# ProProject__EDA__2023-12-29_2024-01-28.net
KiCad netlist of a schematic drawn in EasyEDA Pro
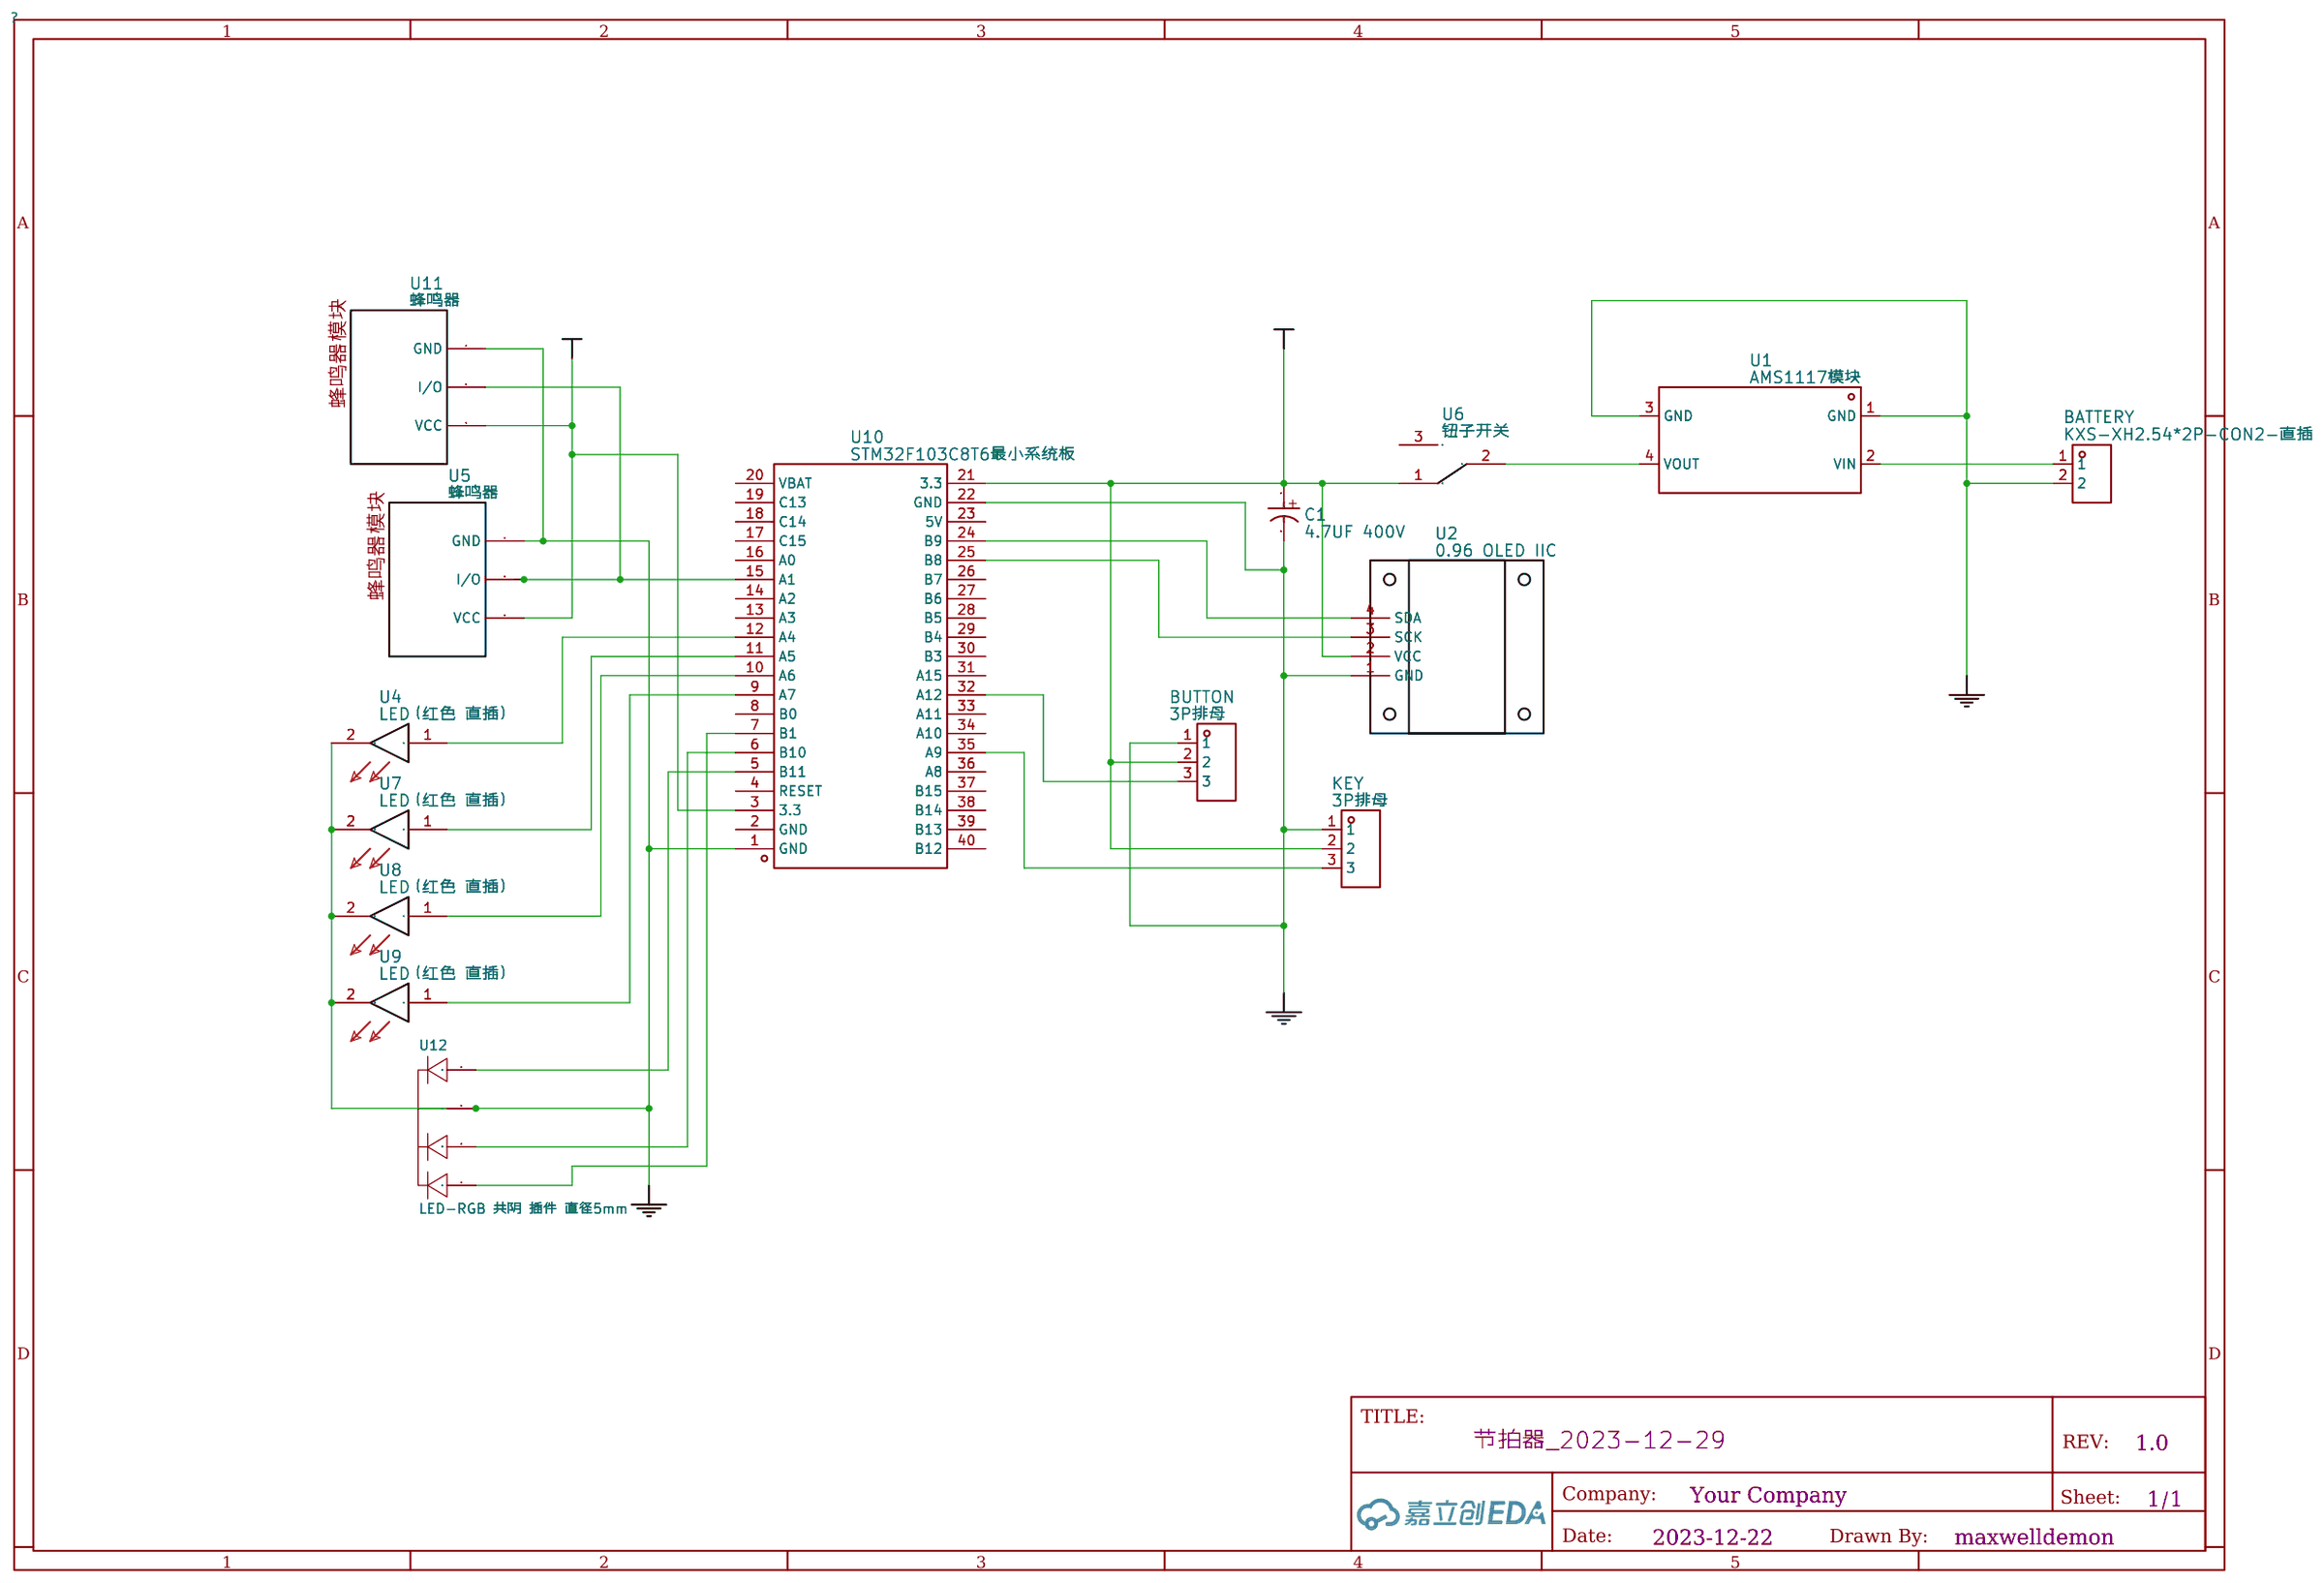
[diagram p0: schematic sheet]

(export (version "E")
  (design (tool "Eeschema 10.0.6"))
  (components
    (comp (ref "BATTERY")
      (value "KXS-XH2.54*2P-CON2-直插")
      (footprint "easyedapro:KXS-XH2.54-CONN-TH_XH2.54-2P")
      (fields (field (name "Manufacturer Part") "KXS-XH2.54*2P_直插"))
      (libsource (lib "easyedapro") (part "KXS-XH2.54*2P-CON2-直插"))
    )
    (comp (ref "BUTTON")
      (value "3P排母")
      (footprint "easyedapro:3P排母")
      (libsource (lib "easyedapro") (part "3P排母"))
    )
    (comp (ref "C1")
      (value "4.7UF 400V")
      (footprint "easyedapro:6X12")
      (libsource (lib "easyedapro") (part "4.7UF 400V"))
    )
    (comp (ref "KEY")
      (value "3P排母")
      (footprint "easyedapro:3P排母")
      (libsource (lib "easyedapro") (part "3P排母"))
    )
    (comp (ref "U1")
      (value "AMS1117模块")
      (footprint "easyedapro:_AMS1117模块")
      (libsource (lib "easyedapro") (part "AMS1117模块"))
    )
    (comp (ref "U2")
      (value "0.96 OLED IIC")
      (footprint "easyedapro:0.96寸OLED模块I2C")
      (fields (field (name "Manufacturer Part") "0.96 OLED"))
      (libsource (lib "easyedapro") (part "0.96 OLED IIC"))
    )
    (comp (ref "U4")
      (value "LED（红色 直插）")
      (footprint "easyedapro:LED直插")
      (libsource (lib "easyedapro") (part "LED（红色 直插）"))
    )
    (comp (ref "U5") (value "蜂鸣器") (footprint "easyedapro:蜂鸣器模块") (libsource (lib "easyedapro") (part "蜂鸣器")))
    (comp (ref "U6")
      (value "钮子开关")
      (footprint "easyedapro:钮子开关钮子开关三脚三档")
      (libsource (lib "easyedapro") (part "钮子开关"))
    )
    (comp (ref "U7")
      (value "LED（红色 直插）")
      (footprint "easyedapro:LED直插")
      (libsource (lib "easyedapro") (part "LED（红色 直插）"))
    )
    (comp (ref "U8")
      (value "LED（红色 直插）")
      (footprint "easyedapro:LED直插")
      (libsource (lib "easyedapro") (part "LED（红色 直插）"))
    )
    (comp (ref "U9")
      (value "LED（红色 直插）")
      (footprint "easyedapro:LED直插")
      (libsource (lib "easyedapro") (part "LED（红色 直插）"))
    )
    (comp (ref "U10")
      (value "STM32F103C8T6最小系统板")
      (footprint "easyedapro:STM32F103C8T6最小系统板PCB图")
      (libsource (lib "easyedapro") (part "STM32F103C8T6最小系统板"))
    )
    (comp (ref "U11")
      (value "蜂鸣器")
      (footprint "easyedapro:蜂鸣器模块")
      (libsource (lib "easyedapro") (part "蜂鸣器"))
    )
    (comp (ref "U12")
      (value "LED-RGB 共阴 插件 直径5mm")
      (footprint "easyedapro:LED-TH_4P-BD5.8-P1.30")
      (libsource (lib "easyedapro") (part "LED-RGB 共阴 插件 直径5MM"))
    )
  )
  (nets
    (net (code "1") (name "GND") (class "Default")
      (node (ref "BATTERY") (pin "2") (pinfunction "2_2") (pintype "unspecified"))
      (node (ref "BUTTON") (pin "1") (pinfunction "1_1") (pintype "unspecified"))
      (node (ref "C1") (pin "2") (pinfunction "2_2") (pintype "input"))
      (node (ref "KEY") (pin "1") (pinfunction "1_1") (pintype "unspecified"))
      (node (ref "U1") (pin "1") (pinfunction "GND_1") (pintype "unspecified"))
      (node (ref "U1") (pin "3") (pinfunction "GND_3") (pintype "unspecified"))
      (node (ref "U10") (pin "1") (pinfunction "GND_1") (pintype "unspecified"))
      (node (ref "U10") (pin "22") (pinfunction "GND_22") (pintype "unspecified"))
      (node (ref "U11") (pin "1") (pinfunction "GND_1") (pintype "unspecified"))
      (node (ref "U12") (pin "2") (pinfunction "-_2") (pintype "input"))
      (node (ref "U2") (pin "1") (pinfunction "GND_1") (pintype "unspecified"))
      (node (ref "U4") (pin "2") (pinfunction "2_2") (pintype "unspecified"))
      (node (ref "U5") (pin "1") (pinfunction "GND_1") (pintype "unspecified"))
      (node (ref "U7") (pin "2") (pinfunction "2_2") (pintype "unspecified"))
      (node (ref "U8") (pin "2") (pinfunction "2_2") (pintype "unspecified"))
      (node (ref "U9") (pin "2") (pinfunction "2_2") (pintype "unspecified"))
    )
    (net (code "2") (name "Net-(U1-VIN)") (class "Default")
      (node (ref "BATTERY") (pin "1") (pinfunction "1_1") (pintype "unspecified"))
      (node (ref "U1") (pin "2") (pinfunction "VIN_2") (pintype "unspecified"))
    )
    (net (code "3") (name "Net-(U1-VOUT)") (class "Default")
      (node (ref "U1") (pin "4") (pinfunction "VOUT_4") (pintype "unspecified"))
      (node (ref "U6") (pin "2") (pinfunction "1_2") (pintype "unspecified"))
    )
    (net (code "4") (name "Net-(U10-A1)") (class "Default")
      (node (ref "U10") (pin "15") (pinfunction "A1_15") (pintype "unspecified"))
      (node (ref "U11") (pin "2") (pinfunction "I/O_2") (pintype "unspecified"))
      (node (ref "U5") (pin "2") (pinfunction "I/O_2") (pintype "unspecified"))
    )
    (net (code "5") (name "Net-(U10-A4)") (class "Default")
      (node (ref "U10") (pin "12") (pinfunction "A4_12") (pintype "unspecified"))
      (node (ref "U4") (pin "1") (pinfunction "1_1") (pintype "unspecified"))
    )
    (net (code "6") (name "Net-(U10-A5)") (class "Default")
      (node (ref "U10") (pin "11") (pinfunction "A5_11") (pintype "unspecified"))
      (node (ref "U7") (pin "1") (pinfunction "1_1") (pintype "unspecified"))
    )
    (net (code "7") (name "Net-(U10-A6)") (class "Default")
      (node (ref "U10") (pin "10") (pinfunction "A6_10") (pintype "unspecified"))
      (node (ref "U8") (pin "1") (pinfunction "1_1") (pintype "unspecified"))
    )
    (net (code "8") (name "Net-(U10-A7)") (class "Default")
      (node (ref "U10") (pin "9") (pinfunction "A7_9") (pintype "unspecified"))
      (node (ref "U9") (pin "1") (pinfunction "1_1") (pintype "unspecified"))
    )
    (net (code "9") (name "Net-(U10-A9)") (class "Default")
      (node (ref "KEY") (pin "3") (pinfunction "3_3") (pintype "unspecified"))
      (node (ref "U10") (pin "35") (pinfunction "A9_35") (pintype "unspecified"))
    )
    (net (code "10") (name "Net-(U10-A12)") (class "Default")
      (node (ref "BUTTON") (pin "3") (pinfunction "3_3") (pintype "unspecified"))
      (node (ref "U10") (pin "32") (pinfunction "A12_32") (pintype "unspecified"))
    )
    (net (code "11") (name "Net-(U10-B1)") (class "Default")
      (node (ref "U10") (pin "7") (pinfunction "B1_7") (pintype "unspecified"))
      (node (ref "U12") (pin "4") (pinfunction "4_4") (pintype "input"))
    )
    (net (code "12") (name "Net-(U10-B8)") (class "Default")
      (node (ref "U10") (pin "25") (pinfunction "B8_25") (pintype "unspecified"))
      (node (ref "U2") (pin "3") (pinfunction "SCK_3") (pintype "unspecified"))
    )
    (net (code "13") (name "Net-(U10-B9)") (class "Default")
      (node (ref "U10") (pin "24") (pinfunction "B9_24") (pintype "unspecified"))
      (node (ref "U2") (pin "4") (pinfunction "SDA_4") (pintype "unspecified"))
    )
    (net (code "14") (name "Net-(U10-B10)") (class "Default")
      (node (ref "U10") (pin "6") (pinfunction "B10_6") (pintype "unspecified"))
      (node (ref "U12") (pin "3") (pinfunction "3_3") (pintype "input"))
    )
    (net (code "15") (name "Net-(U10-B11)") (class "Default")
      (node (ref "U10") (pin "5") (pinfunction "B11_5") (pintype "unspecified"))
      (node (ref "U12") (pin "1") (pinfunction "1_1") (pintype "input"))
    )
    (net (code "16") (name "VCC") (class "Default")
      (node (ref "BUTTON") (pin "2") (pinfunction "2_2") (pintype "unspecified"))
      (node (ref "C1") (pin "1") (pinfunction "1_1") (pintype "input"))
      (node (ref "KEY") (pin "2") (pinfunction "2_2") (pintype "unspecified"))
      (node (ref "U10") (pin "21") (pinfunction "3.3_21") (pintype "unspecified"))
      (node (ref "U10") (pin "3") (pinfunction "3.3_3") (pintype "unspecified"))
      (node (ref "U11") (pin "3") (pinfunction "VCC_3") (pintype "unspecified"))
      (node (ref "U2") (pin "2") (pinfunction "VCC_2") (pintype "unspecified"))
      (node (ref "U5") (pin "3") (pinfunction "VCC_3") (pintype "unspecified"))
      (node (ref "U6") (pin "1") (pinfunction "3_1") (pintype "unspecified"))
    )
    (net (code "17") (name "unconnected-(U6-4-Pad3)") (class "Default")
      (node (ref "U6") (pin "3") (pinfunction "4_3") (pintype "unspecified"))
    )
    (net (code "18") (name "unconnected-(U10-5V-Pad23)") (class "Default")
      (node (ref "U10") (pin "23") (pinfunction "5V_23") (pintype "unspecified"))
    )
    (net (code "19") (name "unconnected-(U10-A0-Pad16)") (class "Default")
      (node (ref "U10") (pin "16") (pinfunction "A0_16") (pintype "unspecified"))
    )
    (net (code "20") (name "unconnected-(U10-A2-Pad14)") (class "Default")
      (node (ref "U10") (pin "14") (pinfunction "A2_14") (pintype "unspecified"))
    )
    (net (code "21") (name "unconnected-(U10-A3-Pad13)") (class "Default")
      (node (ref "U10") (pin "13") (pinfunction "A3_13") (pintype "unspecified"))
    )
    (net (code "22") (name "unconnected-(U10-A8-Pad36)") (class "Default")
      (node (ref "U10") (pin "36") (pinfunction "A8_36") (pintype "unspecified"))
    )
    (net (code "23") (name "unconnected-(U10-A10-Pad34)") (class "Default")
      (node (ref "U10") (pin "34") (pinfunction "A10_34") (pintype "unspecified"))
    )
    (net (code "24") (name "unconnected-(U10-A11-Pad33)") (class "Default")
      (node (ref "U10") (pin "33") (pinfunction "A11_33") (pintype "unspecified"))
    )
    (net (code "25") (name "unconnected-(U10-A15-Pad31)") (class "Default")
      (node (ref "U10") (pin "31") (pinfunction "A15_31") (pintype "unspecified"))
    )
    (net (code "26") (name "unconnected-(U10-B0-Pad8)") (class "Default")
      (node (ref "U10") (pin "8") (pinfunction "B0_8") (pintype "unspecified"))
    )
    (net (code "27") (name "unconnected-(U10-B3-Pad30)") (class "Default")
      (node (ref "U10") (pin "30") (pinfunction "B3_30") (pintype "unspecified"))
    )
    (net (code "28") (name "unconnected-(U10-B4-Pad29)") (class "Default")
      (node (ref "U10") (pin "29") (pinfunction "B4_29") (pintype "unspecified"))
    )
    (net (code "29") (name "unconnected-(U10-B5-Pad28)") (class "Default")
      (node (ref "U10") (pin "28") (pinfunction "B5_28") (pintype "unspecified"))
    )
    (net (code "30") (name "unconnected-(U10-B6-Pad27)") (class "Default")
      (node (ref "U10") (pin "27") (pinfunction "B6_27") (pintype "unspecified"))
    )
    (net (code "31") (name "unconnected-(U10-B7-Pad26)") (class "Default")
      (node (ref "U10") (pin "26") (pinfunction "B7_26") (pintype "unspecified"))
    )
    (net (code "32") (name "unconnected-(U10-B12-Pad40)") (class "Default")
      (node (ref "U10") (pin "40") (pinfunction "B12_40") (pintype "unspecified"))
    )
    (net (code "33") (name "unconnected-(U10-B13-Pad39)") (class "Default")
      (node (ref "U10") (pin "39") (pinfunction "B13_39") (pintype "unspecified"))
    )
    (net (code "34") (name "unconnected-(U10-B14-Pad38)") (class "Default")
      (node (ref "U10") (pin "38") (pinfunction "B14_38") (pintype "unspecified"))
    )
    (net (code "35") (name "unconnected-(U10-B15-Pad37)") (class "Default")
      (node (ref "U10") (pin "37") (pinfunction "B15_37") (pintype "unspecified"))
    )
    (net (code "36") (name "unconnected-(U10-C13-Pad19)") (class "Default")
      (node (ref "U10") (pin "19") (pinfunction "C13_19") (pintype "unspecified"))
    )
    (net (code "37") (name "unconnected-(U10-C14-Pad18)") (class "Default")
      (node (ref "U10") (pin "18") (pinfunction "C14_18") (pintype "unspecified"))
    )
    (net (code "38") (name "unconnected-(U10-C15-Pad17)") (class "Default")
      (node (ref "U10") (pin "17") (pinfunction "C15_17") (pintype "unspecified"))
    )
    (net (code "39") (name "unconnected-(U10-GND-Pad2)") (class "Default")
      (node (ref "U10") (pin "2") (pinfunction "GND_2") (pintype "unspecified"))
    )
    (net (code "40") (name "unconnected-(U10-RESET-Pad4)") (class "Default")
      (node (ref "U10") (pin "4") (pinfunction "RESET_4") (pintype "unspecified"))
    )
    (net (code "41") (name "unconnected-(U10-VBAT-Pad20)") (class "Default")
      (node (ref "U10") (pin "20") (pinfunction "VBAT_20") (pintype "unspecified"))
    )
  )
)
